# v4_0.net
KiCad netlist of a schematic drawn in EAGLE
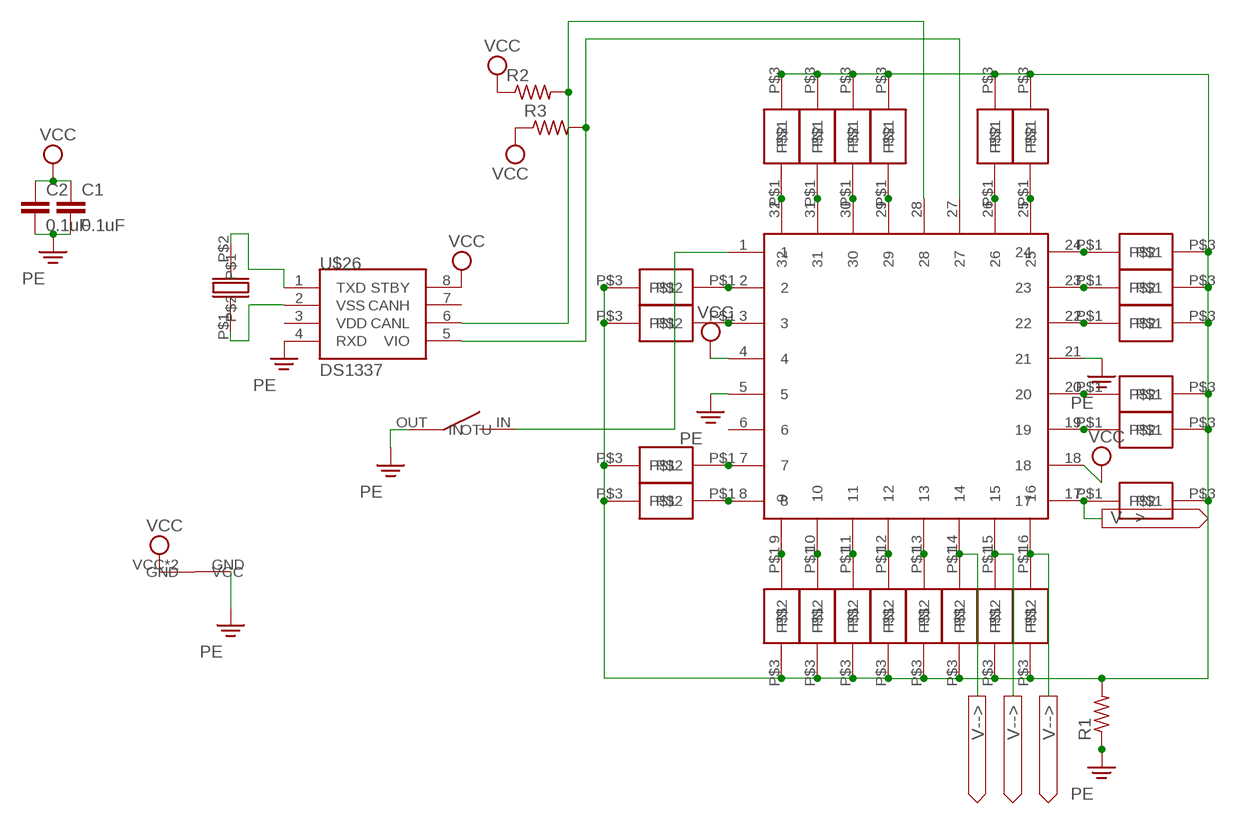
[diagram p0: schematic, sheet 1]

(export (version "E")
  (design (tool "Eeschema 10.0.6"))
  (components
    (comp (ref "C1")
      (value "0.1uF")
      (footprint "eagle-import:C0805K")
      (libsource (lib "eagle-import") (part "C-EUC0805K"))
    )
    (comp (ref "C2")
      (value "0.1uF")
      (footprint "eagle-import:C0805K")
      (libsource (lib "eagle-import") (part "C-EUC0805K"))
    )
    (comp (ref "R1")
      (value "R-US_R0805")
      (footprint "eagle-import:R0805")
      (libsource (lib "eagle-import") (part "R-US_R0805"))
    )
    (comp (ref "R2")
      (value "R-US_R0805")
      (footprint "eagle-import:R0805")
      (libsource (lib "eagle-import") (part "R-US_R0805"))
    )
    (comp (ref "R3")
      (value "R-US_R0805")
      (footprint "eagle-import:R0805")
      (libsource (lib "eagle-import") (part "R-US_R0805"))
    )
    (comp (ref "U$1")
      (value "SMDLED")
      (footprint "eagle-import:SMDLED")
      (libsource (lib "eagle-import") (part "SMDLED"))
    )
    (comp (ref "U$2")
      (value "SMDLED")
      (footprint "eagle-import:SMDLED")
      (libsource (lib "eagle-import") (part "SMDLED"))
    )
    (comp (ref "U$3")
      (value "SMDLED")
      (footprint "eagle-import:SMDLED")
      (libsource (lib "eagle-import") (part "SMDLED"))
    )
    (comp (ref "U$4")
      (value "SMDLED")
      (footprint "eagle-import:SMDLED")
      (libsource (lib "eagle-import") (part "SMDLED"))
    )
    (comp (ref "U$5")
      (value "SMDLED")
      (footprint "eagle-import:SMDLED")
      (libsource (lib "eagle-import") (part "SMDLED"))
    )
    (comp (ref "U$6")
      (value "SMDLED")
      (footprint "eagle-import:SMDLED")
      (libsource (lib "eagle-import") (part "SMDLED"))
    )
    (comp (ref "U$7")
      (value "SMDLED")
      (footprint "eagle-import:SMDLED")
      (libsource (lib "eagle-import") (part "SMDLED"))
    )
    (comp (ref "U$8")
      (value "SMDLED")
      (footprint "eagle-import:SMDLED")
      (libsource (lib "eagle-import") (part "SMDLED"))
    )
    (comp (ref "U$9")
      (value "SMDLED")
      (footprint "eagle-import:SMDLED")
      (libsource (lib "eagle-import") (part "SMDLED"))
    )
    (comp (ref "U$10")
      (value "SMDLED")
      (footprint "eagle-import:SMDLED")
      (libsource (lib "eagle-import") (part "SMDLED"))
    )
    (comp (ref "U$11")
      (value "SMDLED")
      (footprint "eagle-import:SMDLED")
      (libsource (lib "eagle-import") (part "SMDLED"))
    )
    (comp (ref "U$12")
      (value "SMDLED")
      (footprint "eagle-import:SMDLED")
      (libsource (lib "eagle-import") (part "SMDLED"))
    )
    (comp (ref "U$13")
      (value "SMDLED")
      (footprint "eagle-import:SMDLED")
      (libsource (lib "eagle-import") (part "SMDLED"))
    )
    (comp (ref "U$14")
      (value "SMDLED")
      (footprint "eagle-import:SMDLED")
      (libsource (lib "eagle-import") (part "SMDLED"))
    )
    (comp (ref "U$15")
      (value "SMDLED")
      (footprint "eagle-import:SMDLED")
      (libsource (lib "eagle-import") (part "SMDLED"))
    )
    (comp (ref "U$16")
      (value "SMDLED")
      (footprint "eagle-import:SMDLED")
      (libsource (lib "eagle-import") (part "SMDLED"))
    )
    (comp (ref "U$17")
      (value "SMDLED")
      (footprint "eagle-import:SMDLED")
      (libsource (lib "eagle-import") (part "SMDLED"))
    )
    (comp (ref "U$18")
      (value "SMDLED")
      (footprint "eagle-import:SMDLED")
      (libsource (lib "eagle-import") (part "SMDLED"))
    )
    (comp (ref "U$19")
      (value "SMDLED")
      (footprint "eagle-import:SMDLED")
      (libsource (lib "eagle-import") (part "SMDLED"))
    )
    (comp (ref "U$20")
      (value "SMDLED")
      (footprint "eagle-import:SMDLED")
      (libsource (lib "eagle-import") (part "SMDLED"))
    )
    (comp (ref "U$21")
      (value "SMDLED")
      (footprint "eagle-import:SMDLED")
      (libsource (lib "eagle-import") (part "SMDLED"))
    )
    (comp (ref "U$22")
      (value "SMDLED")
      (footprint "eagle-import:SMDLED")
      (libsource (lib "eagle-import") (part "SMDLED"))
    )
    (comp (ref "U$23")
      (value "SMDLED")
      (footprint "eagle-import:SMDLED")
      (libsource (lib "eagle-import") (part "SMDLED"))
    )
    (comp (ref "U$24")
      (value "SMDLED")
      (footprint "eagle-import:SMDLED")
      (libsource (lib "eagle-import") (part "SMDLED"))
    )
    (comp (ref "U$25")
      (value "ATTINY88")
      (footprint "eagle-import:32-TQFT")
      (libsource (lib "eagle-import") (part "ATTINY88"))
    )
    (comp (ref "U$26")
      (value "DS1337")
      (footprint "eagle-import:8-SOIC")
      (libsource (lib "eagle-import") (part "DS1337"))
    )
    (comp (ref "U$27")
      (value "BAT2009")
      (footprint "eagle-import:BAT2009")
      (libsource (lib "eagle-import") (part "BAT2009"))
    )
    (comp (ref "U$28")
      (value "INT2")
      (footprint "eagle-import:INT2")
      (libsource (lib "eagle-import") (part "INT2"))
    )
    (comp (ref "U$29")
      (value "SMDCRYSTAL")
      (footprint "eagle-import:SMDCRYSTAL")
      (libsource (lib "eagle-import") (part "SMDCRYSTAL"))
    )
  )
  (nets
    (net (code "1") (name "Net-(U$1-P$2)") (class "Default")
      (node (ref "R1") (pin "2") (pinfunction "2_2") (pintype "passive"))
      (node (ref "U$1") (pin "P$3") (pinfunction "P$2_P$3") (pintype "bidirectional"))
      (node (ref "U$10") (pin "P$3") (pinfunction "P$2_P$3") (pintype "bidirectional"))
      (node (ref "U$11") (pin "P$3") (pinfunction "P$2_P$3") (pintype "bidirectional"))
      (node (ref "U$12") (pin "P$3") (pinfunction "P$2_P$3") (pintype "bidirectional"))
      (node (ref "U$13") (pin "P$3") (pinfunction "P$2_P$3") (pintype "bidirectional"))
      (node (ref "U$14") (pin "P$3") (pinfunction "P$2_P$3") (pintype "bidirectional"))
      (node (ref "U$15") (pin "P$3") (pinfunction "P$2_P$3") (pintype "bidirectional"))
      (node (ref "U$16") (pin "P$3") (pinfunction "P$2_P$3") (pintype "bidirectional"))
      (node (ref "U$17") (pin "P$3") (pinfunction "P$2_P$3") (pintype "bidirectional"))
      (node (ref "U$18") (pin "P$3") (pinfunction "P$2_P$3") (pintype "bidirectional"))
      (node (ref "U$19") (pin "P$3") (pinfunction "P$2_P$3") (pintype "bidirectional"))
      (node (ref "U$2") (pin "P$3") (pinfunction "P$2_P$3") (pintype "bidirectional"))
      (node (ref "U$20") (pin "P$3") (pinfunction "P$2_P$3") (pintype "bidirectional"))
      (node (ref "U$21") (pin "P$3") (pinfunction "P$2_P$3") (pintype "bidirectional"))
      (node (ref "U$22") (pin "P$3") (pinfunction "P$2_P$3") (pintype "bidirectional"))
      (node (ref "U$23") (pin "P$3") (pinfunction "P$2_P$3") (pintype "bidirectional"))
      (node (ref "U$24") (pin "P$3") (pinfunction "P$2_P$3") (pintype "bidirectional"))
      (node (ref "U$3") (pin "P$3") (pinfunction "P$2_P$3") (pintype "bidirectional"))
      (node (ref "U$4") (pin "P$3") (pinfunction "P$2_P$3") (pintype "bidirectional"))
      (node (ref "U$5") (pin "P$3") (pinfunction "P$2_P$3") (pintype "bidirectional"))
      (node (ref "U$6") (pin "P$3") (pinfunction "P$2_P$3") (pintype "bidirectional"))
      (node (ref "U$7") (pin "P$3") (pinfunction "P$2_P$3") (pintype "bidirectional"))
      (node (ref "U$8") (pin "P$3") (pinfunction "P$2_P$3") (pintype "bidirectional"))
      (node (ref "U$9") (pin "P$3") (pinfunction "P$2_P$3") (pintype "bidirectional"))
    )
    (net (code "2") (name "Net-(U$1-PadP$1)") (class "Default")
      (node (ref "U$1") (pin "P$1") (pinfunction "P$1_P$1") (pintype "bidirectional"))
      (node (ref "U$25") (pin "12") (pinfunction "12_12") (pintype "bidirectional"))
    )
    (net (code "3") (name "Net-(U$2-PadP$1)") (class "Default")
      (node (ref "U$2") (pin "P$1") (pinfunction "P$1_P$1") (pintype "bidirectional"))
      (node (ref "U$25") (pin "13") (pinfunction "13_13") (pintype "bidirectional"))
    )
    (net (code "4") (name "Net-(U$10-PadP$1)") (class "Default")
      (node (ref "U$10") (pin "P$1") (pinfunction "P$1_P$1") (pintype "bidirectional"))
      (node (ref "U$25") (pin "20") (pinfunction "20_20") (pintype "bidirectional"))
    )
    (net (code "5") (name "Net-(U$11-PadP$1)") (class "Default")
      (node (ref "U$11") (pin "P$1") (pinfunction "P$1_P$1") (pintype "bidirectional"))
      (node (ref "U$25") (pin "17") (pinfunction "17_17") (pintype "bidirectional"))
    )
    (net (code "6") (name "Net-(U$12-PadP$1)") (class "Default")
      (node (ref "U$12") (pin "P$1") (pinfunction "P$1_P$1") (pintype "bidirectional"))
      (node (ref "U$25") (pin "19") (pinfunction "19_19") (pintype "bidirectional"))
    )
    (net (code "7") (name "Net-(U$13-PadP$1)") (class "Default")
      (node (ref "U$13") (pin "P$1") (pinfunction "P$1_P$1") (pintype "bidirectional"))
      (node (ref "U$25") (pin "30") (pinfunction "30_30") (pintype "bidirectional"))
    )
    (net (code "8") (name "Net-(U$14-PadP$1)") (class "Default")
      (node (ref "U$14") (pin "P$1") (pinfunction "P$1_P$1") (pintype "bidirectional"))
      (node (ref "U$25") (pin "31") (pinfunction "31_31") (pintype "bidirectional"))
    )
    (net (code "9") (name "Net-(U$15-PadP$1)") (class "Default")
      (node (ref "U$15") (pin "P$1") (pinfunction "P$1_P$1") (pintype "bidirectional"))
      (node (ref "U$25") (pin "32") (pinfunction "32_32") (pintype "bidirectional"))
    )
    (net (code "10") (name "Net-(U$16-PadP$1)") (class "Default")
      (node (ref "U$16") (pin "P$1") (pinfunction "P$1_P$1") (pintype "bidirectional"))
      (node (ref "U$25") (pin "2") (pinfunction "2_2") (pintype "bidirectional"))
    )
    (net (code "11") (name "Net-(U$17-PadP$1)") (class "Default")
      (node (ref "U$17") (pin "P$1") (pinfunction "P$1_P$1") (pintype "bidirectional"))
      (node (ref "U$25") (pin "3") (pinfunction "3_3") (pintype "bidirectional"))
    )
    (net (code "12") (name "Net-(U$18-PadP$1)") (class "Default")
      (node (ref "U$18") (pin "P$1") (pinfunction "P$1_P$1") (pintype "bidirectional"))
      (node (ref "U$25") (pin "9") (pinfunction "9_9") (pintype "bidirectional"))
    )
    (net (code "13") (name "Net-(U$19-PadP$1)") (class "Default")
      (node (ref "U$19") (pin "P$1") (pinfunction "P$1_P$1") (pintype "bidirectional"))
      (node (ref "U$25") (pin "10") (pinfunction "10_10") (pintype "bidirectional"))
    )
    (net (code "14") (name "Net-(U$20-PadP$1)") (class "Default")
      (node (ref "U$20") (pin "P$1") (pinfunction "P$1_P$1") (pintype "bidirectional"))
      (node (ref "U$25") (pin "11") (pinfunction "11_11") (pintype "bidirectional"))
    )
    (net (code "15") (name "Net-(U$21-PadP$1)") (class "Default")
      (node (ref "U$21") (pin "P$1") (pinfunction "P$1_P$1") (pintype "bidirectional"))
      (node (ref "U$25") (pin "22") (pinfunction "22_22") (pintype "bidirectional"))
    )
    (net (code "16") (name "Net-(U$22-PadP$1)") (class "Default")
      (node (ref "U$22") (pin "P$1") (pinfunction "P$1_P$1") (pintype "bidirectional"))
      (node (ref "U$25") (pin "23") (pinfunction "23_23") (pintype "bidirectional"))
    )
    (net (code "17") (name "Net-(U$23-PadP$1)") (class "Default")
      (node (ref "U$23") (pin "P$1") (pinfunction "P$1_P$1") (pintype "bidirectional"))
      (node (ref "U$25") (pin "29") (pinfunction "29_29") (pintype "bidirectional"))
    )
    (net (code "18") (name "Net-(U$24-PadP$1)") (class "Default")
      (node (ref "U$24") (pin "P$1") (pinfunction "P$1_P$1") (pintype "bidirectional"))
      (node (ref "U$25") (pin "26") (pinfunction "26_26") (pintype "bidirectional"))
    )
    (net (code "19") (name "Net-(U$25-Pad1)") (class "Default")
      (node (ref "U$25") (pin "1") (pinfunction "1_1") (pintype "bidirectional"))
      (node (ref "U$28") (pin "IN") (pinfunction "IN_IN") (pintype "bidirectional"))
    )
    (net (code "20") (name "Net-(U$25-Pad7)") (class "Default")
      (node (ref "U$25") (pin "7") (pinfunction "7_7") (pintype "bidirectional"))
      (node (ref "U$7") (pin "P$1") (pinfunction "P$1_P$1") (pintype "bidirectional"))
    )
    (net (code "21") (name "Net-(U$25-Pad8)") (class "Default")
      (node (ref "U$25") (pin "8") (pinfunction "8_8") (pintype "bidirectional"))
      (node (ref "U$8") (pin "P$1") (pinfunction "P$1_P$1") (pintype "bidirectional"))
    )
    (net (code "22") (name "Net-(U$25-Pad14)") (class "Default")
      (node (ref "U$25") (pin "14") (pinfunction "14_14") (pintype "bidirectional"))
      (node (ref "U$3") (pin "P$1") (pinfunction "P$1_P$1") (pintype "bidirectional"))
    )
    (net (code "23") (name "Net-(U$25-Pad15)") (class "Default")
      (node (ref "U$25") (pin "15") (pinfunction "15_15") (pintype "bidirectional"))
      (node (ref "U$4") (pin "P$1") (pinfunction "P$1_P$1") (pintype "bidirectional"))
    )
    (net (code "24") (name "Net-(U$25-Pad16)") (class "Default")
      (node (ref "U$25") (pin "16") (pinfunction "16_16") (pintype "bidirectional"))
      (node (ref "U$5") (pin "P$1") (pinfunction "P$1_P$1") (pintype "bidirectional"))
    )
    (net (code "25") (name "Net-(U$25-Pad24)") (class "Default")
      (node (ref "U$25") (pin "24") (pinfunction "24_24") (pintype "bidirectional"))
      (node (ref "U$6") (pin "P$1") (pinfunction "P$1_P$1") (pintype "bidirectional"))
    )
    (net (code "26") (name "Net-(U$25-Pad25)") (class "Default")
      (node (ref "U$25") (pin "25") (pinfunction "25_25") (pintype "bidirectional"))
      (node (ref "U$9") (pin "P$1") (pinfunction "P$1_P$1") (pintype "bidirectional"))
    )
    (net (code "27") (name "Net-(U$26-CANL)") (class "Default")
      (node (ref "R2") (pin "2") (pinfunction "2_2") (pintype "passive"))
      (node (ref "U$25") (pin "28") (pinfunction "28_28") (pintype "bidirectional"))
      (node (ref "U$26") (pin "6") (pinfunction "CANL_6") (pintype "bidirectional"))
    )
    (net (code "28") (name "Net-(U$26-TXD)") (class "Default")
      (node (ref "U$26") (pin "1") (pinfunction "TXD_1") (pintype "bidirectional"))
      (node (ref "U$29") (pin "P$2") (pinfunction "P$2_P$2") (pintype "bidirectional"))
    )
    (net (code "29") (name "Net-(U$26-VIO)") (class "Default")
      (node (ref "R3") (pin "2") (pinfunction "2_2") (pintype "passive"))
      (node (ref "U$25") (pin "27") (pinfunction "27_27") (pintype "bidirectional"))
      (node (ref "U$26") (pin "5") (pinfunction "VIO_5") (pintype "bidirectional"))
    )
    (net (code "30") (name "Net-(U$26-VSS)") (class "Default")
      (node (ref "U$26") (pin "2") (pinfunction "VSS_2") (pintype "bidirectional"))
      (node (ref "U$29") (pin "P$1") (pinfunction "P$1_P$1") (pintype "bidirectional"))
    )
    (net (code "31") (name "PE") (class "Default")
      (node (ref "C1") (pin "2") (pinfunction "2_2") (pintype "passive"))
      (node (ref "C2") (pin "2") (pinfunction "2_2") (pintype "passive"))
      (node (ref "R1") (pin "1") (pinfunction "1_1") (pintype "passive"))
      (node (ref "U$25") (pin "21") (pinfunction "21_21") (pintype "bidirectional"))
      (node (ref "U$25") (pin "5") (pinfunction "5_5") (pintype "bidirectional"))
      (node (ref "U$26") (pin "4") (pinfunction "RXD_4") (pintype "bidirectional"))
      (node (ref "U$27") (pin "GND") (pinfunction "GND_GND") (pintype "bidirectional"))
      (node (ref "U$28") (pin "OUT") (pinfunction "OTU_OUT") (pintype "bidirectional"))
    )
    (net (code "32") (name "VCC") (class "Default")
      (node (ref "C1") (pin "1") (pinfunction "1_1") (pintype "passive"))
      (node (ref "C2") (pin "1") (pinfunction "1_1") (pintype "passive"))
      (node (ref "R2") (pin "1") (pinfunction "1_1") (pintype "passive"))
      (node (ref "R3") (pin "1") (pinfunction "1_1") (pintype "passive"))
      (node (ref "U$25") (pin "18") (pinfunction "18_18") (pintype "bidirectional"))
      (node (ref "U$25") (pin "4") (pinfunction "4_4") (pintype "bidirectional"))
      (node (ref "U$26") (pin "8") (pinfunction "STBY_8") (pintype "bidirectional"))
      (node (ref "U$27") (pin "VCC") (pinfunction "VCC_VCC") (pintype "bidirectional"))
      (node (ref "U$27") (pin "VCC2") (pinfunction "VCC_VCC2") (pintype "bidirectional"))
    )
    (net (code "33") (name "unconnected-(U$25-Pad6)") (class "Default")
      (node (ref "U$25") (pin "6") (pinfunction "6_6") (pintype "bidirectional"))
    )
    (net (code "34") (name "unconnected-(U$26-CANH-Pad7)") (class "Default")
      (node (ref "U$26") (pin "7") (pinfunction "CANH_7") (pintype "bidirectional"))
    )
    (net (code "35") (name "unconnected-(U$26-VDD-Pad3)") (class "Default")
      (node (ref "U$26") (pin "3") (pinfunction "VDD_3") (pintype "bidirectional"))
    )
  )
)
